# Project.net
KiCad netlist of a schematic drawn in EAGLE
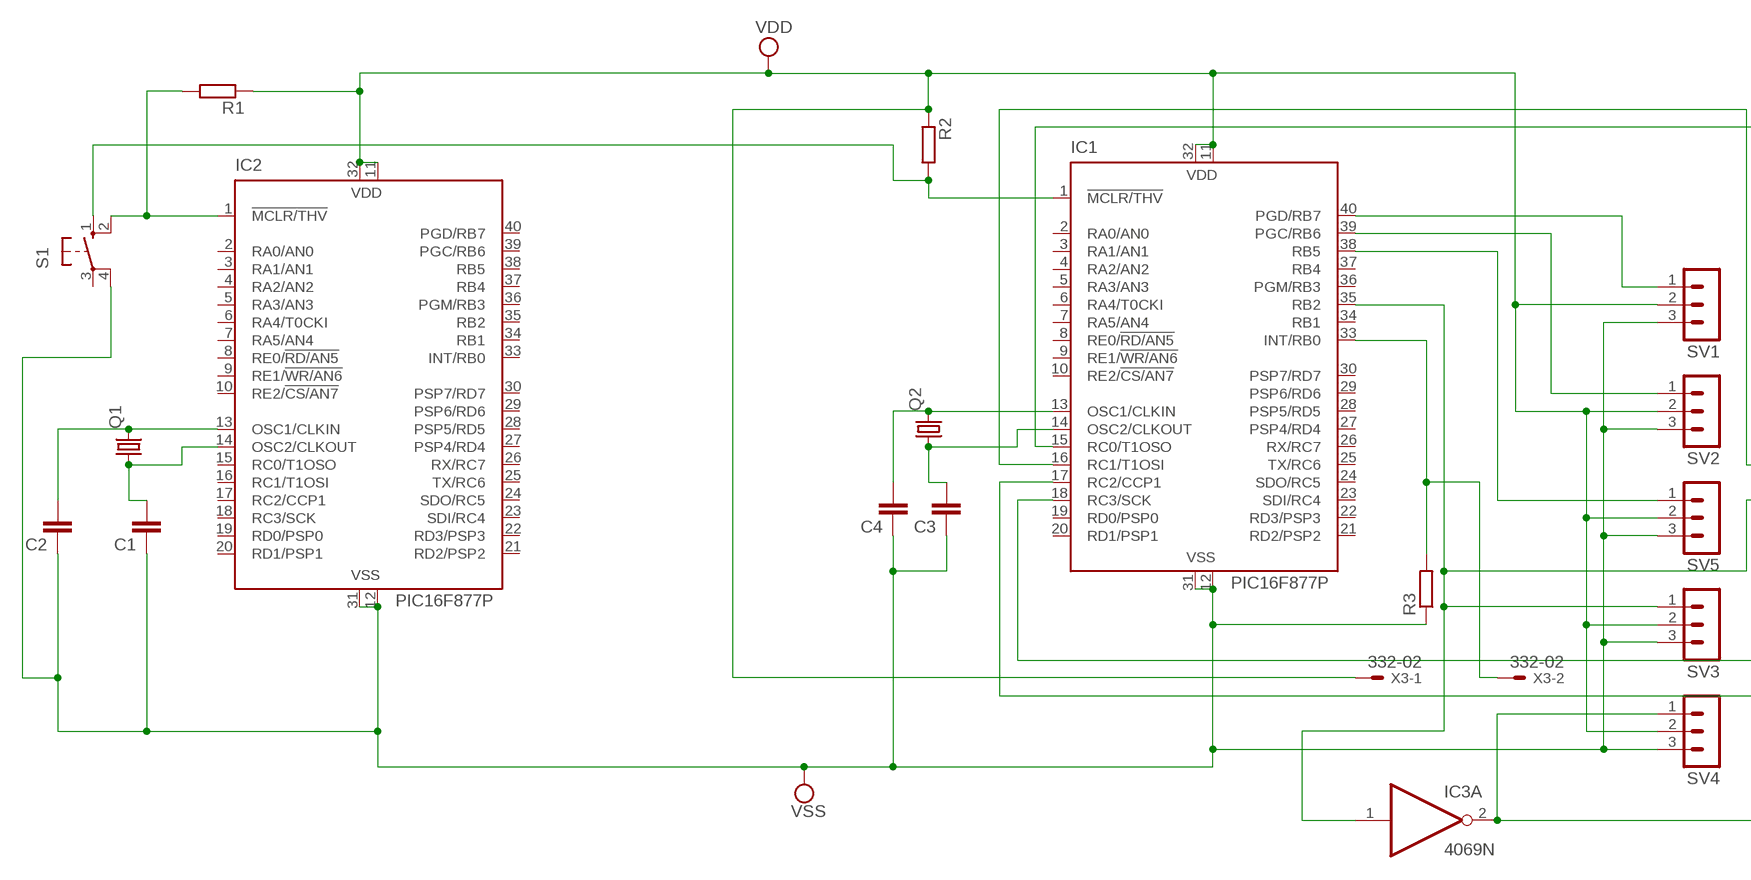
[diagram p0: schematic, sheet 1, part 1 of 2]
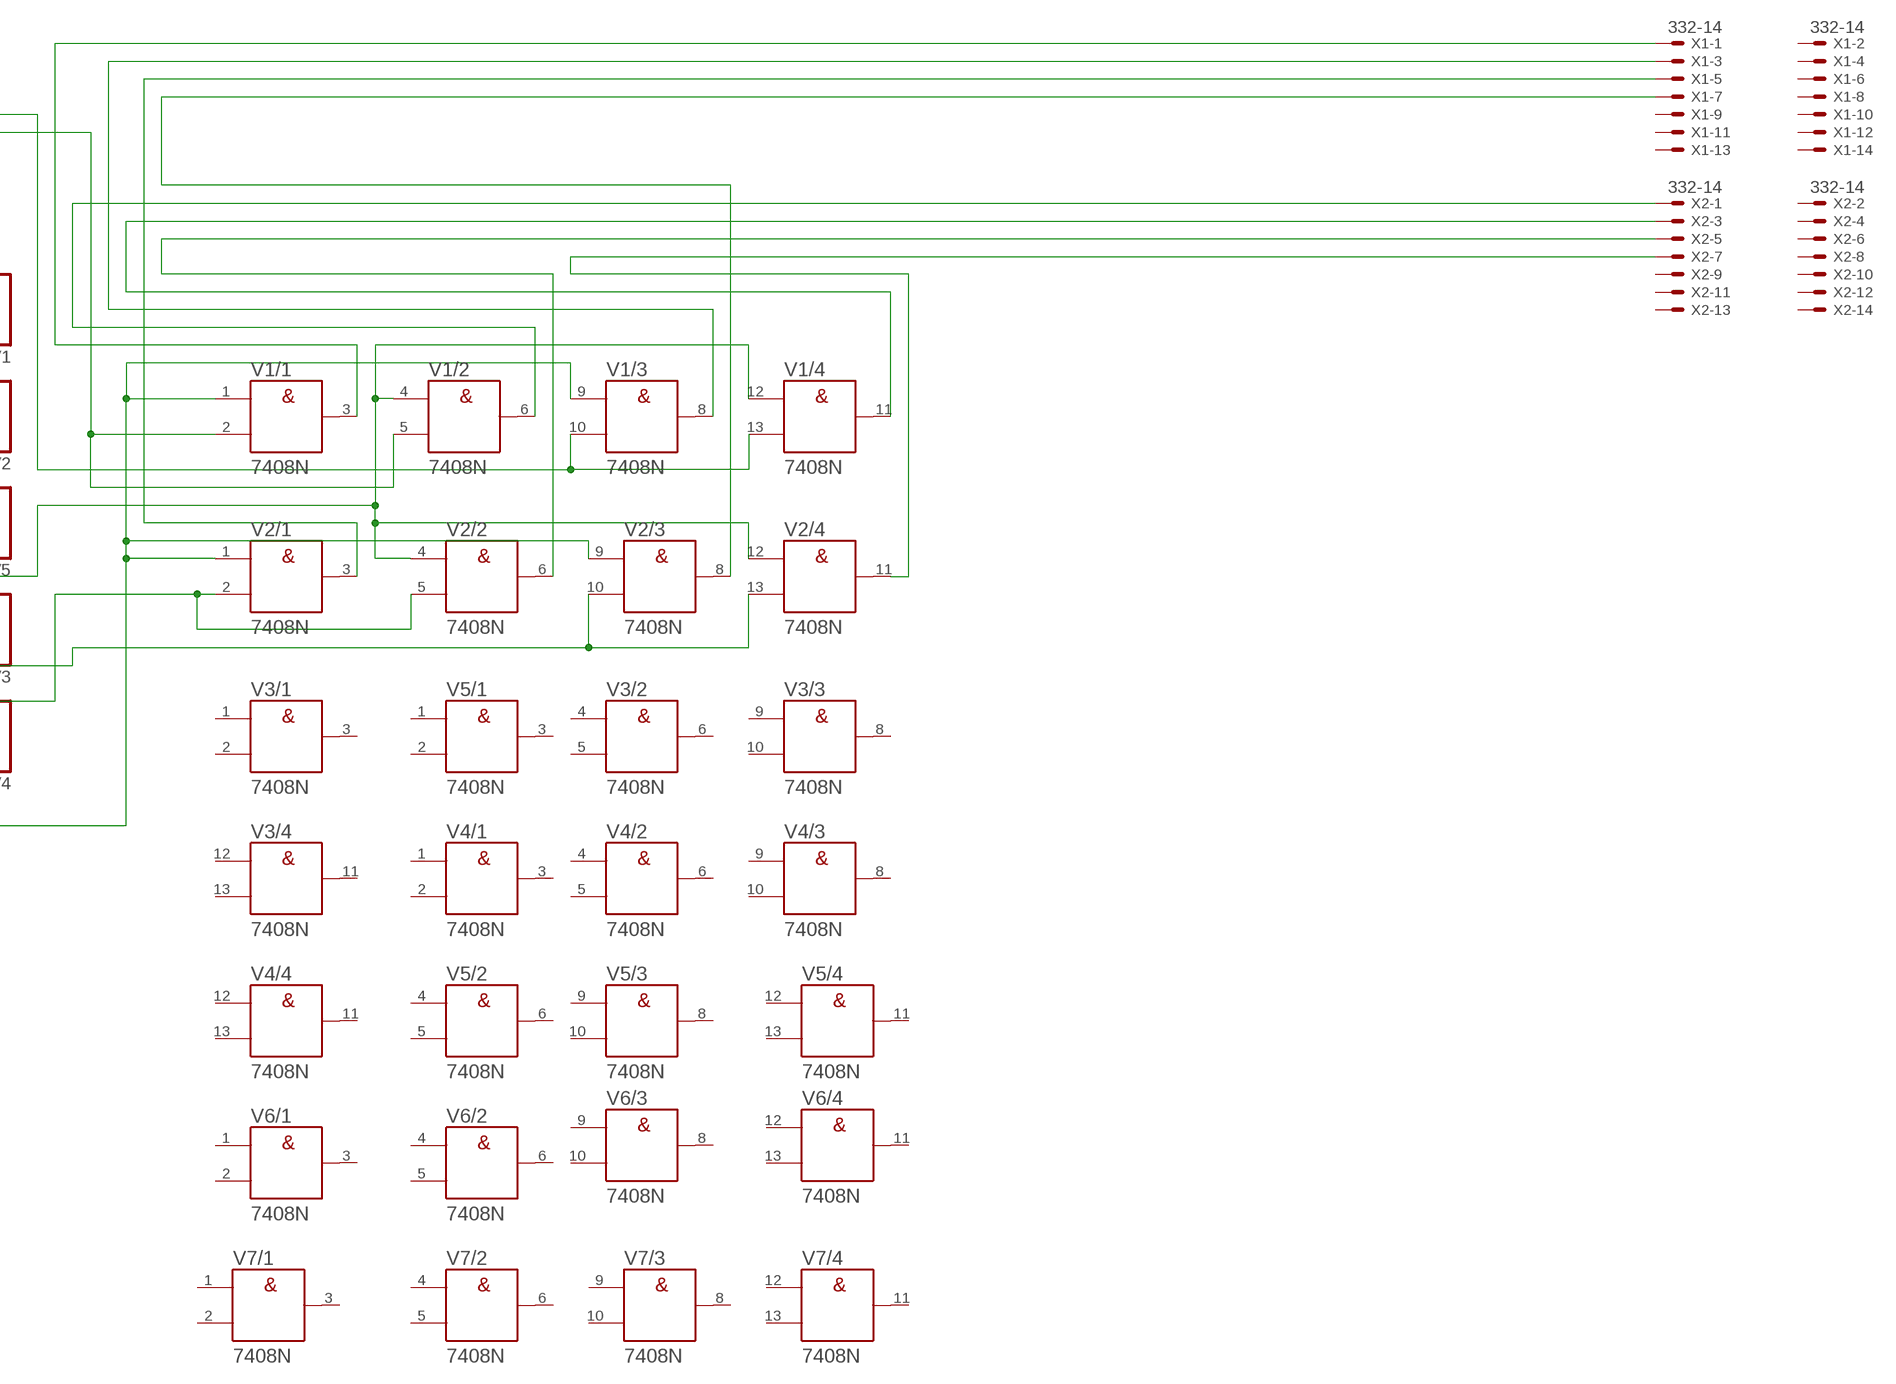
[diagram p1: schematic, sheet 1, part 2 of 2]

(export (version "E")
  (design (tool "Eeschema 10.0.6"))
  (components
    (comp (ref "C1")
      (value "C7.5/3")
      (footprint "eagle-import:C7.5B3")
      (libsource (lib "eagle-import") (part "C7.5/3"))
    )
    (comp (ref "C2")
      (value "C7.5/3")
      (footprint "eagle-import:C7.5B3")
      (libsource (lib "eagle-import") (part "C7.5/3"))
    )
    (comp (ref "C3")
      (value "C7.5/3")
      (footprint "eagle-import:C7.5B3")
      (libsource (lib "eagle-import") (part "C7.5/3"))
    )
    (comp (ref "C4")
      (value "C7.5/3")
      (footprint "eagle-import:C7.5B3")
      (libsource (lib "eagle-import") (part "C7.5/3"))
    )
    (comp (ref "IC1")
      (value "PIC16F877P")
      (footprint "eagle-import:DIL40")
      (fields (field (name "MF") "MICROCHIP") (field (name "MPN") "PIC16F877-04/P"))
      (libsource (lib "eagle-import") (part "PIC16F87P7"))
    )
    (comp (ref "IC2")
      (value "PIC16F877P")
      (footprint "eagle-import:DIL40")
      (fields (field (name "MF") "MICROCHIP") (field (name "MPN") "PIC16F877-04/P"))
      (libsource (lib "eagle-import") (part "PIC16F87P7"))
    )
    (comp (ref "IC3")
      (value "4069N")
      (footprint "eagle-import:DIL14")
      (libsource (lib "eagle-import") (part "4069N"))
    )
    (comp (ref "Q1")
      (value "CRYSTALHC49U-V")
      (footprint "eagle-import:HC49U-V")
      (libsource (lib "eagle-import") (part "CRYSTALHC49U-V"))
    )
    (comp (ref "Q2")
      (value "CRYSTALHC49U-V")
      (footprint "eagle-import:HC49U-V")
      (libsource (lib "eagle-import") (part "CRYSTALHC49U-V"))
    )
    (comp (ref "R1")
      (value "R-EU_0207/10")
      (footprint "eagle-import:0207_10")
      (libsource (lib "eagle-import") (part "R-EU_0207/10"))
    )
    (comp (ref "R2")
      (value "R-EU_0207/10")
      (footprint "eagle-import:0207_10")
      (libsource (lib "eagle-import") (part "R-EU_0207/10"))
    )
    (comp (ref "R3")
      (value "R-EU_0207/10")
      (footprint "eagle-import:0207_10")
      (libsource (lib "eagle-import") (part "R-EU_0207/10"))
    )
    (comp (ref "S1")
      (value "10-XX")
      (footprint "eagle-import:B3F-10XX")
      (fields (field (name "MPN") "B3F-1000"))
      (libsource (lib "eagle-import") (part "10-XX"))
    )
    (comp (ref "SV1")
      (value "MA03-1")
      (footprint "eagle-import:MA03-1")
      (libsource (lib "eagle-import") (part "MA03-1"))
    )
    (comp (ref "SV2")
      (value "MA03-1")
      (footprint "eagle-import:MA03-1")
      (libsource (lib "eagle-import") (part "MA03-1"))
    )
    (comp (ref "SV3")
      (value "MA03-1")
      (footprint "eagle-import:MA03-1")
      (libsource (lib "eagle-import") (part "MA03-1"))
    )
    (comp (ref "SV4")
      (value "MA03-1")
      (footprint "eagle-import:MA03-1")
      (libsource (lib "eagle-import") (part "MA03-1"))
    )
    (comp (ref "SV5")
      (value "MA03-1")
      (footprint "eagle-import:MA03-1")
      (libsource (lib "eagle-import") (part "MA03-1"))
    )
    (comp (ref "V1")
      (value "7408N")
      (footprint "eagle-import:DIL14")
      (libsource (lib "eagle-import") (part "7408N"))
    )
    (comp (ref "V2")
      (value "7408N")
      (footprint "eagle-import:DIL14")
      (libsource (lib "eagle-import") (part "7408N"))
    )
    (comp (ref "V3")
      (value "7408N")
      (footprint "eagle-import:DIL14")
      (libsource (lib "eagle-import") (part "7408N"))
    )
    (comp (ref "V4")
      (value "7408N")
      (footprint "eagle-import:DIL14")
      (libsource (lib "eagle-import") (part "7408N"))
    )
    (comp (ref "V5")
      (value "7408N")
      (footprint "eagle-import:DIL14")
      (libsource (lib "eagle-import") (part "7408N"))
    )
    (comp (ref "V6")
      (value "7408N")
      (footprint "eagle-import:DIL14")
      (libsource (lib "eagle-import") (part "7408N"))
    )
    (comp (ref "V7")
      (value "7408N")
      (footprint "eagle-import:DIL14")
      (libsource (lib "eagle-import") (part "7408N"))
    )
    (comp (ref "X1")
      (value "332-14")
      (footprint "eagle-import:332-14")
      (libsource (lib "eagle-import") (part "332-14"))
    )
    (comp (ref "X2")
      (value "332-14")
      (footprint "eagle-import:332-14")
      (libsource (lib "eagle-import") (part "332-14"))
    )
    (comp (ref "X3")
      (value "332-02")
      (footprint "eagle-import:332-02")
      (libsource (lib "eagle-import") (part "332-02"))
    )
  )
  (nets
    (net (code "1") (name "Net-(IC1-INT{slash}RB0)") (class "Default")
      (node (ref "IC1") (pin "33") (pinfunction "INT/RB0_33") (pintype "bidirectional"))
      (node (ref "R3") (pin "2") (pinfunction "2_2") (pintype "passive"))
      (node (ref "X3") (pin "2") (pinfunction "S_2") (pintype "passive"))
    )
    (net (code "2") (name "Net-(IC1-OSC1{slash}CLKIN)") (class "Default")
      (node (ref "C4") (pin "2") (pinfunction "2_2") (pintype "passive"))
      (node (ref "IC1") (pin "13") (pinfunction "OSC1/CLKIN_13") (pintype "input"))
      (node (ref "Q2") (pin "2") (pinfunction "2_2") (pintype "passive"))
    )
    (net (code "3") (name "Net-(IC1-OSC2{slash}CLKOUT)") (class "Default")
      (node (ref "C3") (pin "2") (pinfunction "2_2") (pintype "passive"))
      (node (ref "IC1") (pin "14") (pinfunction "OSC2/CLKOUT_14") (pintype "output"))
      (node (ref "Q2") (pin "1") (pinfunction "1_1") (pintype "passive"))
    )
    (net (code "4") (name "Net-(IC1-PGC{slash}RB6)") (class "Default")
      (node (ref "IC1") (pin "39") (pinfunction "PGC/RB6_39") (pintype "bidirectional"))
      (node (ref "SV2") (pin "1") (pinfunction "1_1") (pintype "passive"))
    )
    (net (code "5") (name "Net-(IC1-PGD{slash}RB7)") (class "Default")
      (node (ref "IC1") (pin "40") (pinfunction "PGD/RB7_40") (pintype "bidirectional"))
      (node (ref "SV1") (pin "1") (pinfunction "1_1") (pintype "passive"))
    )
    (net (code "6") (name "Net-(IC1-RB2)") (class "Default")
      (node (ref "IC1") (pin "35") (pinfunction "RB2_35") (pintype "bidirectional"))
      (node (ref "IC3") (pin "1") (pinfunction "I_1") (pintype "input"))
      (node (ref "SV3") (pin "1") (pinfunction "1_1") (pintype "passive"))
      (node (ref "V1") (pin "12") (pinfunction "A_12") (pintype "input"))
      (node (ref "V1") (pin "4") (pinfunction "A_4") (pintype "input"))
      (node (ref "V2") (pin "12") (pinfunction "A_12") (pintype "input"))
      (node (ref "V2") (pin "4") (pinfunction "A_4") (pintype "input"))
    )
    (net (code "7") (name "Net-(IC1-RB5)") (class "Default")
      (node (ref "IC1") (pin "38") (pinfunction "RB5_38") (pintype "bidirectional"))
      (node (ref "SV5") (pin "1") (pinfunction "1_1") (pintype "passive"))
    )
    (net (code "8") (name "Net-(IC1-RC0{slash}T1OSO)") (class "Default")
      (node (ref "IC1") (pin "15") (pinfunction "RC0/T1OSO_15") (pintype "bidirectional"))
      (node (ref "V1") (pin "2") (pinfunction "B_2") (pintype "input"))
      (node (ref "V1") (pin "5") (pinfunction "B_5") (pintype "input"))
    )
    (net (code "9") (name "Net-(IC1-RC1{slash}T1OSI)") (class "Default")
      (node (ref "IC1") (pin "16") (pinfunction "RC1/T1OSI_16") (pintype "bidirectional"))
      (node (ref "V1") (pin "10") (pinfunction "B_10") (pintype "input"))
      (node (ref "V1") (pin "13") (pinfunction "B_13") (pintype "input"))
    )
    (net (code "10") (name "Net-(IC1-RC2{slash}CCP1)") (class "Default")
      (node (ref "IC1") (pin "17") (pinfunction "RC2/CCP1_17") (pintype "bidirectional"))
      (node (ref "V2") (pin "2") (pinfunction "B_2") (pintype "input"))
      (node (ref "V2") (pin "5") (pinfunction "B_5") (pintype "input"))
    )
    (net (code "11") (name "Net-(IC1-RC3{slash}SCK)") (class "Default")
      (node (ref "IC1") (pin "18") (pinfunction "RC3/SCK_18") (pintype "bidirectional"))
      (node (ref "V2") (pin "10") (pinfunction "B_10") (pintype "input"))
      (node (ref "V2") (pin "13") (pinfunction "B_13") (pintype "input"))
    )
    (net (code "12") (name "Net-(IC1-~{MCLR{slash}THV})") (class "Default")
      (node (ref "IC1") (pin "1") (pinfunction "~{MCLR/THV}_1") (pintype "input"))
      (node (ref "R2") (pin "2") (pinfunction "2_2") (pintype "passive"))
      (node (ref "S1") (pin "1") (pinfunction "S_1") (pintype "passive"))
    )
    (net (code "13") (name "Net-(IC2-OSC1{slash}CLKIN)") (class "Default")
      (node (ref "C2") (pin "2") (pinfunction "2_2") (pintype "passive"))
      (node (ref "IC2") (pin "13") (pinfunction "OSC1/CLKIN_13") (pintype "input"))
      (node (ref "Q1") (pin "2") (pinfunction "2_2") (pintype "passive"))
    )
    (net (code "14") (name "Net-(IC2-OSC2{slash}CLKOUT)") (class "Default")
      (node (ref "C1") (pin "2") (pinfunction "2_2") (pintype "passive"))
      (node (ref "IC2") (pin "14") (pinfunction "OSC2/CLKOUT_14") (pintype "output"))
      (node (ref "Q1") (pin "1") (pinfunction "1_1") (pintype "passive"))
    )
    (net (code "15") (name "Net-(IC2-~{MCLR{slash}THV})") (class "Default")
      (node (ref "IC2") (pin "1") (pinfunction "~{MCLR/THV}_1") (pintype "input"))
      (node (ref "R1") (pin "2") (pinfunction "2_2") (pintype "passive"))
      (node (ref "S1") (pin "2") (pinfunction "S1_2") (pintype "passive"))
    )
    (net (code "16") (name "Net-(IC3A-O)") (class "Default")
      (node (ref "IC3") (pin "2") (pinfunction "O_2") (pintype "output"))
      (node (ref "SV4") (pin "1") (pinfunction "1_1") (pintype "passive"))
      (node (ref "V1") (pin "1") (pinfunction "A_1") (pintype "input"))
      (node (ref "V1") (pin "9") (pinfunction "A_9") (pintype "input"))
      (node (ref "V2") (pin "1") (pinfunction "A_1") (pintype "input"))
      (node (ref "V2") (pin "9") (pinfunction "A_9") (pintype "input"))
    )
    (net (code "17") (name "Net-(V1C-Y)") (class "Default")
      (node (ref "V1") (pin "3") (pinfunction "Y_3") (pintype "output"))
      (node (ref "X1") (pin "1") (pinfunction "S_1") (pintype "passive"))
    )
    (net (code "18") (name "Net-(V1D-Y)") (class "Default")
      (node (ref "V1") (pin "6") (pinfunction "Y_6") (pintype "output"))
      (node (ref "X2") (pin "1") (pinfunction "S_1") (pintype "passive"))
    )
    (net (code "19") (name "Net-(V1E-Y)") (class "Default")
      (node (ref "V1") (pin "8") (pinfunction "Y_8") (pintype "output"))
      (node (ref "X1") (pin "3") (pinfunction "S_3") (pintype "passive"))
    )
    (net (code "20") (name "Net-(V1F-Y)") (class "Default")
      (node (ref "V1") (pin "11") (pinfunction "Y_11") (pintype "output"))
      (node (ref "X2") (pin "3") (pinfunction "S_3") (pintype "passive"))
    )
    (net (code "21") (name "Net-(V2C-Y)") (class "Default")
      (node (ref "V2") (pin "3") (pinfunction "Y_3") (pintype "output"))
      (node (ref "X1") (pin "5") (pinfunction "S_5") (pintype "passive"))
    )
    (net (code "22") (name "Net-(V2D-Y)") (class "Default")
      (node (ref "V2") (pin "6") (pinfunction "Y_6") (pintype "output"))
      (node (ref "X2") (pin "5") (pinfunction "S_5") (pintype "passive"))
    )
    (net (code "23") (name "Net-(V2E-Y)") (class "Default")
      (node (ref "V2") (pin "8") (pinfunction "Y_8") (pintype "output"))
      (node (ref "X1") (pin "7") (pinfunction "S_7") (pintype "passive"))
    )
    (net (code "24") (name "Net-(V2F-Y)") (class "Default")
      (node (ref "V2") (pin "11") (pinfunction "Y_11") (pintype "output"))
      (node (ref "X2") (pin "7") (pinfunction "S_7") (pintype "passive"))
    )
    (net (code "25") (name "VDD") (class "Default")
      (node (ref "IC1") (pin "11") (pinfunction "VDD_11") (pintype "power_in"))
      (node (ref "IC1") (pin "32") (pinfunction "VDD_32") (pintype "power_in"))
      (node (ref "IC2") (pin "11") (pinfunction "VDD_11") (pintype "power_in"))
      (node (ref "IC2") (pin "32") (pinfunction "VDD_32") (pintype "power_in"))
      (node (ref "R1") (pin "1") (pinfunction "1_1") (pintype "passive"))
      (node (ref "R2") (pin "1") (pinfunction "1_1") (pintype "passive"))
      (node (ref "SV1") (pin "2") (pinfunction "2_2") (pintype "passive"))
      (node (ref "SV2") (pin "2") (pinfunction "2_2") (pintype "passive"))
      (node (ref "SV3") (pin "2") (pinfunction "2_2") (pintype "passive"))
      (node (ref "SV4") (pin "2") (pinfunction "2_2") (pintype "passive"))
      (node (ref "SV5") (pin "2") (pinfunction "2_2") (pintype "passive"))
      (node (ref "X3") (pin "1") (pinfunction "S_1") (pintype "passive"))
    )
    (net (code "26") (name "VSS") (class "Default")
      (node (ref "C1") (pin "1") (pinfunction "1_1") (pintype "passive"))
      (node (ref "C2") (pin "1") (pinfunction "1_1") (pintype "passive"))
      (node (ref "C3") (pin "1") (pinfunction "1_1") (pintype "passive"))
      (node (ref "C4") (pin "1") (pinfunction "1_1") (pintype "passive"))
      (node (ref "IC1") (pin "12") (pinfunction "VSS_12") (pintype "power_in"))
      (node (ref "IC1") (pin "31") (pinfunction "VSS_31") (pintype "power_in"))
      (node (ref "IC2") (pin "12") (pinfunction "VSS_12") (pintype "power_in"))
      (node (ref "IC2") (pin "31") (pinfunction "VSS_31") (pintype "power_in"))
      (node (ref "R3") (pin "1") (pinfunction "1_1") (pintype "passive"))
      (node (ref "S1") (pin "4") (pinfunction "P1_4") (pintype "passive"))
      (node (ref "SV1") (pin "3") (pinfunction "3_3") (pintype "passive"))
      (node (ref "SV2") (pin "3") (pinfunction "3_3") (pintype "passive"))
      (node (ref "SV3") (pin "3") (pinfunction "3_3") (pintype "passive"))
      (node (ref "SV4") (pin "3") (pinfunction "3_3") (pintype "passive"))
      (node (ref "SV5") (pin "3") (pinfunction "3_3") (pintype "passive"))
    )
    (net (code "27") (name "unconnected-(IC1-PGM{slash}RB3-Pad36)") (class "Default")
      (node (ref "IC1") (pin "36") (pinfunction "PGM/RB3_36") (pintype "bidirectional"))
    )
    (net (code "28") (name "unconnected-(IC1-PSP4{slash}RD4-Pad27)") (class "Default")
      (node (ref "IC1") (pin "27") (pinfunction "PSP4/RD4_27") (pintype "bidirectional"))
    )
    (net (code "29") (name "unconnected-(IC1-PSP5{slash}RD5-Pad28)") (class "Default")
      (node (ref "IC1") (pin "28") (pinfunction "PSP5/RD5_28") (pintype "bidirectional"))
    )
    (net (code "30") (name "unconnected-(IC1-PSP6{slash}RD6-Pad29)") (class "Default")
      (node (ref "IC1") (pin "29") (pinfunction "PSP6/RD6_29") (pintype "bidirectional"))
    )
    (net (code "31") (name "unconnected-(IC1-PSP7{slash}RD7-Pad30)") (class "Default")
      (node (ref "IC1") (pin "30") (pinfunction "PSP7/RD7_30") (pintype "bidirectional"))
    )
    (net (code "32") (name "unconnected-(IC1-RA0{slash}AN0-Pad2)") (class "Default")
      (node (ref "IC1") (pin "2") (pinfunction "RA0/AN0_2") (pintype "bidirectional"))
    )
    (net (code "33") (name "unconnected-(IC1-RA1{slash}AN1-Pad3)") (class "Default")
      (node (ref "IC1") (pin "3") (pinfunction "RA1/AN1_3") (pintype "bidirectional"))
    )
    (net (code "34") (name "unconnected-(IC1-RA2{slash}AN2-Pad4)") (class "Default")
      (node (ref "IC1") (pin "4") (pinfunction "RA2/AN2_4") (pintype "bidirectional"))
    )
    (net (code "35") (name "unconnected-(IC1-RA3{slash}AN3-Pad5)") (class "Default")
      (node (ref "IC1") (pin "5") (pinfunction "RA3/AN3_5") (pintype "bidirectional"))
    )
    (net (code "36") (name "unconnected-(IC1-RA4{slash}T0CKI-Pad6)") (class "Default")
      (node (ref "IC1") (pin "6") (pinfunction "RA4/T0CKI_6") (pintype "bidirectional"))
    )
    (net (code "37") (name "unconnected-(IC1-RA5{slash}AN4-Pad7)") (class "Default")
      (node (ref "IC1") (pin "7") (pinfunction "RA5/AN4_7") (pintype "bidirectional"))
    )
    (net (code "38") (name "unconnected-(IC1-RB1-Pad34)") (class "Default")
      (node (ref "IC1") (pin "34") (pinfunction "RB1_34") (pintype "bidirectional"))
    )
    (net (code "39") (name "unconnected-(IC1-RB4-Pad37)") (class "Default")
      (node (ref "IC1") (pin "37") (pinfunction "RB4_37") (pintype "bidirectional"))
    )
    (net (code "40") (name "unconnected-(IC1-RD0{slash}PSP0-Pad19)") (class "Default")
      (node (ref "IC1") (pin "19") (pinfunction "RD0/PSP0_19") (pintype "bidirectional"))
    )
    (net (code "41") (name "unconnected-(IC1-RD1{slash}PSP1-Pad20)") (class "Default")
      (node (ref "IC1") (pin "20") (pinfunction "RD1/PSP1_20") (pintype "bidirectional"))
    )
    (net (code "42") (name "unconnected-(IC1-RD2{slash}PSP2-Pad21)") (class "Default")
      (node (ref "IC1") (pin "21") (pinfunction "RD2/PSP2_21") (pintype "bidirectional"))
    )
    (net (code "43") (name "unconnected-(IC1-RD3{slash}PSP3-Pad22)") (class "Default")
      (node (ref "IC1") (pin "22") (pinfunction "RD3/PSP3_22") (pintype "bidirectional"))
    )
    (net (code "44") (name "unconnected-(IC1-RE0{slash}~{RD{slash}AN5}-Pad8)") (class "Default")
      (node (ref "IC1") (pin "8") (pinfunction "RE0/~{RD/AN5}_8") (pintype "bidirectional"))
    )
    (net (code "45") (name "unconnected-(IC1-RE1{slash}~{WR{slash}AN6}-Pad9)") (class "Default")
      (node (ref "IC1") (pin "9") (pinfunction "RE1/~{WR/AN6}_9") (pintype "bidirectional"))
    )
    (net (code "46") (name "unconnected-(IC1-RE2{slash}~{CS{slash}AN7}-Pad10)") (class "Default")
      (node (ref "IC1") (pin "10") (pinfunction "RE2/~{CS/AN7}_10") (pintype "bidirectional"))
    )
    (net (code "47") (name "unconnected-(IC1-RX{slash}RC7-Pad26)") (class "Default")
      (node (ref "IC1") (pin "26") (pinfunction "RX/RC7_26") (pintype "bidirectional"))
    )
    (net (code "48") (name "unconnected-(IC1-SDI{slash}RC4-Pad23)") (class "Default")
      (node (ref "IC1") (pin "23") (pinfunction "SDI/RC4_23") (pintype "bidirectional"))
    )
    (net (code "49") (name "unconnected-(IC1-SDO{slash}RC5-Pad24)") (class "Default")
      (node (ref "IC1") (pin "24") (pinfunction "SDO/RC5_24") (pintype "bidirectional"))
    )
    (net (code "50") (name "unconnected-(IC1-TX{slash}RC6-Pad25)") (class "Default")
      (node (ref "IC1") (pin "25") (pinfunction "TX/RC6_25") (pintype "bidirectional"))
    )
    (net (code "51") (name "unconnected-(IC2-INT{slash}RB0-Pad33)") (class "Default")
      (node (ref "IC2") (pin "33") (pinfunction "INT/RB0_33") (pintype "bidirectional"))
    )
    (net (code "52") (name "unconnected-(IC2-PGC{slash}RB6-Pad39)") (class "Default")
      (node (ref "IC2") (pin "39") (pinfunction "PGC/RB6_39") (pintype "bidirectional"))
    )
    (net (code "53") (name "unconnected-(IC2-PGD{slash}RB7-Pad40)") (class "Default")
      (node (ref "IC2") (pin "40") (pinfunction "PGD/RB7_40") (pintype "bidirectional"))
    )
    (net (code "54") (name "unconnected-(IC2-PGM{slash}RB3-Pad36)") (class "Default")
      (node (ref "IC2") (pin "36") (pinfunction "PGM/RB3_36") (pintype "bidirectional"))
    )
    (net (code "55") (name "unconnected-(IC2-PSP4{slash}RD4-Pad27)") (class "Default")
      (node (ref "IC2") (pin "27") (pinfunction "PSP4/RD4_27") (pintype "bidirectional"))
    )
    (net (code "56") (name "unconnected-(IC2-PSP5{slash}RD5-Pad28)") (class "Default")
      (node (ref "IC2") (pin "28") (pinfunction "PSP5/RD5_28") (pintype "bidirectional"))
    )
    (net (code "57") (name "unconnected-(IC2-PSP6{slash}RD6-Pad29)") (class "Default")
      (node (ref "IC2") (pin "29") (pinfunction "PSP6/RD6_29") (pintype "bidirectional"))
    )
    (net (code "58") (name "unconnected-(IC2-PSP7{slash}RD7-Pad30)") (class "Default")
      (node (ref "IC2") (pin "30") (pinfunction "PSP7/RD7_30") (pintype "bidirectional"))
    )
    (net (code "59") (name "unconnected-(IC2-RA0{slash}AN0-Pad2)") (class "Default")
      (node (ref "IC2") (pin "2") (pinfunction "RA0/AN0_2") (pintype "bidirectional"))
    )
    (net (code "60") (name "unconnected-(IC2-RA1{slash}AN1-Pad3)") (class "Default")
      (node (ref "IC2") (pin "3") (pinfunction "RA1/AN1_3") (pintype "bidirectional"))
    )
    (net (code "61") (name "unconnected-(IC2-RA2{slash}AN2-Pad4)") (class "Default")
      (node (ref "IC2") (pin "4") (pinfunction "RA2/AN2_4") (pintype "bidirectional"))
    )
    (net (code "62") (name "unconnected-(IC2-RA3{slash}AN3-Pad5)") (class "Default")
      (node (ref "IC2") (pin "5") (pinfunction "RA3/AN3_5") (pintype "bidirectional"))
    )
    (net (code "63") (name "unconnected-(IC2-RA4{slash}T0CKI-Pad6)") (class "Default")
      (node (ref "IC2") (pin "6") (pinfunction "RA4/T0CKI_6") (pintype "bidirectional"))
    )
    (net (code "64") (name "unconnected-(IC2-RA5{slash}AN4-Pad7)") (class "Default")
      (node (ref "IC2") (pin "7") (pinfunction "RA5/AN4_7") (pintype "bidirectional"))
    )
    (net (code "65") (name "unconnected-(IC2-RB1-Pad34)") (class "Default")
      (node (ref "IC2") (pin "34") (pinfunction "RB1_34") (pintype "bidirectional"))
    )
    (net (code "66") (name "unconnected-(IC2-RB2-Pad35)") (class "Default")
      (node (ref "IC2") (pin "35") (pinfunction "RB2_35") (pintype "bidirectional"))
    )
    (net (code "67") (name "unconnected-(IC2-RB4-Pad37)") (class "Default")
      (node (ref "IC2") (pin "37") (pinfunction "RB4_37") (pintype "bidirectional"))
    )
    (net (code "68") (name "unconnected-(IC2-RB5-Pad38)") (class "Default")
      (node (ref "IC2") (pin "38") (pinfunction "RB5_38") (pintype "bidirectional"))
    )
    (net (code "69") (name "unconnected-(IC2-RC0{slash}T1OSO-Pad15)") (class "Default")
      (node (ref "IC2") (pin "15") (pinfunction "RC0/T1OSO_15") (pintype "bidirectional"))
    )
    (net (code "70") (name "unconnected-(IC2-RC1{slash}T1OSI-Pad16)") (class "Default")
      (node (ref "IC2") (pin "16") (pinfunction "RC1/T1OSI_16") (pintype "bidirectional"))
    )
    (net (code "71") (name "unconnected-(IC2-RC2{slash}CCP1-Pad17)") (class "Default")
      (node (ref "IC2") (pin "17") (pinfunction "RC2/CCP1_17") (pintype "bidirectional"))
    )
    (net (code "72") (name "unconnected-(IC2-RC3{slash}SCK-Pad18)") (class "Default")
      (node (ref "IC2") (pin "18") (pinfunction "RC3/SCK_18") (pintype "bidirectional"))
    )
    (net (code "73") (name "unconnected-(IC2-RD0{slash}PSP0-Pad19)") (class "Default")
      (node (ref "IC2") (pin "19") (pinfunction "RD0/PSP0_19") (pintype "bidirectional"))
    )
    (net (code "74") (name "unconnected-(IC2-RD1{slash}PSP1-Pad20)") (class "Default")
      (node (ref "IC2") (pin "20") (pinfunction "RD1/PSP1_20") (pintype "bidirectional"))
    )
    (net (code "75") (name "unconnected-(IC2-RD2{slash}PSP2-Pad21)") (class "Default")
      (node (ref "IC2") (pin "21") (pinfunction "RD2/PSP2_21") (pintype "bidirectional"))
    )
    (net (code "76") (name "unconnected-(IC2-RD3{slash}PSP3-Pad22)") (class "Default")
      (node (ref "IC2") (pin "22") (pinfunction "RD3/PSP3_22") (pintype "bidirectional"))
    )
    (net (code "77") (name "unconnected-(IC2-RE0{slash}~{RD{slash}AN5}-Pad8)") (class "Default")
      (node (ref "IC2") (pin "8") (pinfunction "RE0/~{RD/AN5}_8") (pintype "bidirectional"))
    )
    (net (code "78") (name "unconnected-(IC2-RE1{slash}~{WR{slash}AN6}-Pad9)") (class "Default")
      (node (ref "IC2") (pin "9") (pinfunction "RE1/~{WR/AN6}_9") (pintype "bidirectional"))
    )
    (net (code "79") (name "unconnected-(IC2-RE2{slash}~{CS{slash}AN7}-Pad10)") (class "Default")
      (node (ref "IC2") (pin "10") (pinfunction "RE2/~{CS/AN7}_10") (pintype "bidirectional"))
    )
    (net (code "80") (name "unconnected-(IC2-RX{slash}RC7-Pad26)") (class "Default")
      (node (ref "IC2") (pin "26") (pinfunction "RX/RC7_26") (pintype "bidirectional"))
    )
    (net (code "81") (name "unconnected-(IC2-SDI{slash}RC4-Pad23)") (class "Default")
      (node (ref "IC2") (pin "23") (pinfunction "SDI/RC4_23") (pintype "bidirectional"))
    )
    (net (code "82") (name "unconnected-(IC2-SDO{slash}RC5-Pad24)") (class "Default")
      (node (ref "IC2") (pin "24") (pinfunction "SDO/RC5_24") (pintype "bidirectional"))
    )
    (net (code "83") (name "unconnected-(IC2-TX{slash}RC6-Pad25)") (class "Default")
      (node (ref "IC2") (pin "25") (pinfunction "TX/RC6_25") (pintype "bidirectional"))
    )
    (net (code "84") (name "unconnected-(S1-P-Pad3)") (class "Default")
      (node (ref "S1") (pin "3") (pinfunction "P_3") (pintype "passive"))
    )
    (net (code "85") (name "unconnected-(V3C-A-Pad1)") (class "Default")
      (node (ref "V3") (pin "1") (pinfunction "A_1") (pintype "input"))
    )
    (net (code "86") (name "unconnected-(V3C-B-Pad2)") (class "Default")
      (node (ref "V3") (pin "2") (pinfunction "B_2") (pintype "input"))
    )
    (net (code "87") (name "unconnected-(V3C-Y-Pad3)") (class "Default")
      (node (ref "V3") (pin "3") (pinfunction "Y_3") (pintype "output"))
    )
    (net (code "88") (name "unconnected-(V3D-A-Pad4)") (class "Default")
      (node (ref "V3") (pin "4") (pinfunction "A_4") (pintype "input"))
    )
    (net (code "89") (name "unconnected-(V3D-B-Pad5)") (class "Default")
      (node (ref "V3") (pin "5") (pinfunction "B_5") (pintype "input"))
    )
    (net (code "90") (name "unconnected-(V3D-Y-Pad6)") (class "Default")
      (node (ref "V3") (pin "6") (pinfunction "Y_6") (pintype "output"))
    )
    (net (code "91") (name "unconnected-(V3E-A-Pad9)") (class "Default")
      (node (ref "V3") (pin "9") (pinfunction "A_9") (pintype "input"))
    )
    (net (code "92") (name "unconnected-(V3E-B-Pad10)") (class "Default")
      (node (ref "V3") (pin "10") (pinfunction "B_10") (pintype "input"))
    )
    (net (code "93") (name "unconnected-(V3E-Y-Pad8)") (class "Default")
      (node (ref "V3") (pin "8") (pinfunction "Y_8") (pintype "output"))
    )
    (net (code "94") (name "unconnected-(V3F-A-Pad12)") (class "Default")
      (node (ref "V3") (pin "12") (pinfunction "A_12") (pintype "input"))
    )
    (net (code "95") (name "unconnected-(V3F-B-Pad13)") (class "Default")
      (node (ref "V3") (pin "13") (pinfunction "B_13") (pintype "input"))
    )
    (net (code "96") (name "unconnected-(V3F-Y-Pad11)") (class "Default")
      (node (ref "V3") (pin "11") (pinfunction "Y_11") (pintype "output"))
    )
    (net (code "97") (name "unconnected-(V4C-A-Pad1)") (class "Default")
      (node (ref "V4") (pin "1") (pinfunction "A_1") (pintype "input"))
    )
    (net (code "98") (name "unconnected-(V4C-B-Pad2)") (class "Default")
      (node (ref "V4") (pin "2") (pinfunction "B_2") (pintype "input"))
    )
    (net (code "99") (name "unconnected-(V4C-Y-Pad3)") (class "Default")
      (node (ref "V4") (pin "3") (pinfunction "Y_3") (pintype "output"))
    )
    (net (code "100") (name "unconnected-(V4D-A-Pad4)") (class "Default")
      (node (ref "V4") (pin "4") (pinfunction "A_4") (pintype "input"))
    )
    (net (code "101") (name "unconnected-(V4D-B-Pad5)") (class "Default")
      (node (ref "V4") (pin "5") (pinfunction "B_5") (pintype "input"))
    )
    (net (code "102") (name "unconnected-(V4D-Y-Pad6)") (class "Default")
      (node (ref "V4") (pin "6") (pinfunction "Y_6") (pintype "output"))
    )
    (net (code "103") (name "unconnected-(V4E-A-Pad9)") (class "Default")
      (node (ref "V4") (pin "9") (pinfunction "A_9") (pintype "input"))
    )
    (net (code "104") (name "unconnected-(V4E-B-Pad10)") (class "Default")
      (node (ref "V4") (pin "10") (pinfunction "B_10") (pintype "input"))
    )
    (net (code "105") (name "unconnected-(V4E-Y-Pad8)") (class "Default")
      (node (ref "V4") (pin "8") (pinfunction "Y_8") (pintype "output"))
    )
    (net (code "106") (name "unconnected-(V4F-A-Pad12)") (class "Default")
      (node (ref "V4") (pin "12") (pinfunction "A_12") (pintype "input"))
    )
    (net (code "107") (name "unconnected-(V4F-B-Pad13)") (class "Default")
      (node (ref "V4") (pin "13") (pinfunction "B_13") (pintype "input"))
    )
    (net (code "108") (name "unconnected-(V4F-Y-Pad11)") (class "Default")
      (node (ref "V4") (pin "11") (pinfunction "Y_11") (pintype "output"))
    )
    (net (code "109") (name "unconnected-(V5C-A-Pad1)") (class "Default")
      (node (ref "V5") (pin "1") (pinfunction "A_1") (pintype "input"))
    )
    (net (code "110") (name "unconnected-(V5C-B-Pad2)") (class "Default")
      (node (ref "V5") (pin "2") (pinfunction "B_2") (pintype "input"))
    )
    (net (code "111") (name "unconnected-(V5C-Y-Pad3)") (class "Default")
      (node (ref "V5") (pin "3") (pinfunction "Y_3") (pintype "output"))
    )
    (net (code "112") (name "unconnected-(V5D-A-Pad4)") (class "Default")
      (node (ref "V5") (pin "4") (pinfunction "A_4") (pintype "input"))
    )
    (net (code "113") (name "unconnected-(V5D-B-Pad5)") (class "Default")
      (node (ref "V5") (pin "5") (pinfunction "B_5") (pintype "input"))
    )
    (net (code "114") (name "unconnected-(V5D-Y-Pad6)") (class "Default")
      (node (ref "V5") (pin "6") (pinfunction "Y_6") (pintype "output"))
    )
    (net (code "115") (name "unconnected-(V5E-A-Pad9)") (class "Default")
      (node (ref "V5") (pin "9") (pinfunction "A_9") (pintype "input"))
    )
    (net (code "116") (name "unconnected-(V5E-B-Pad10)") (class "Default")
      (node (ref "V5") (pin "10") (pinfunction "B_10") (pintype "input"))
    )
    (net (code "117") (name "unconnected-(V5E-Y-Pad8)") (class "Default")
      (node (ref "V5") (pin "8") (pinfunction "Y_8") (pintype "output"))
    )
    (net (code "118") (name "unconnected-(V5F-A-Pad12)") (class "Default")
      (node (ref "V5") (pin "12") (pinfunction "A_12") (pintype "input"))
    )
    (net (code "119") (name "unconnected-(V5F-B-Pad13)") (class "Default")
      (node (ref "V5") (pin "13") (pinfunction "B_13") (pintype "input"))
    )
    (net (code "120") (name "unconnected-(V5F-Y-Pad11)") (class "Default")
      (node (ref "V5") (pin "11") (pinfunction "Y_11") (pintype "output"))
    )
    (net (code "121") (name "unconnected-(V6C-A-Pad1)") (class "Default")
      (node (ref "V6") (pin "1") (pinfunction "A_1") (pintype "input"))
    )
    (net (code "122") (name "unconnected-(V6C-B-Pad2)") (class "Default")
      (node (ref "V6") (pin "2") (pinfunction "B_2") (pintype "input"))
    )
    (net (code "123") (name "unconnected-(V6C-Y-Pad3)") (class "Default")
      (node (ref "V6") (pin "3") (pinfunction "Y_3") (pintype "output"))
    )
    (net (code "124") (name "unconnected-(V6D-A-Pad4)") (class "Default")
      (node (ref "V6") (pin "4") (pinfunction "A_4") (pintype "input"))
    )
    (net (code "125") (name "unconnected-(V6D-B-Pad5)") (class "Default")
      (node (ref "V6") (pin "5") (pinfunction "B_5") (pintype "input"))
    )
    (net (code "126") (name "unconnected-(V6D-Y-Pad6)") (class "Default")
      (node (ref "V6") (pin "6") (pinfunction "Y_6") (pintype "output"))
    )
    (net (code "127") (name "unconnected-(V6E-A-Pad9)") (class "Default")
      (node (ref "V6") (pin "9") (pinfunction "A_9") (pintype "input"))
    )
    (net (code "128") (name "unconnected-(V6E-B-Pad10)") (class "Default")
      (node (ref "V6") (pin "10") (pinfunction "B_10") (pintype "input"))
    )
    (net (code "129") (name "unconnected-(V6E-Y-Pad8)") (class "Default")
      (node (ref "V6") (pin "8") (pinfunction "Y_8") (pintype "output"))
    )
    (net (code "130") (name "unconnected-(V6F-A-Pad12)") (class "Default")
      (node (ref "V6") (pin "12") (pinfunction "A_12") (pintype "input"))
    )
    (net (code "131") (name "unconnected-(V6F-B-Pad13)") (class "Default")
      (node (ref "V6") (pin "13") (pinfunction "B_13") (pintype "input"))
    )
    (net (code "132") (name "unconnected-(V6F-Y-Pad11)") (class "Default")
      (node (ref "V6") (pin "11") (pinfunction "Y_11") (pintype "output"))
    )
    (net (code "133") (name "unconnected-(V7C-A-Pad1)") (class "Default")
      (node (ref "V7") (pin "1") (pinfunction "A_1") (pintype "input"))
    )
    (net (code "134") (name "unconnected-(V7C-B-Pad2)") (class "Default")
      (node (ref "V7") (pin "2") (pinfunction "B_2") (pintype "input"))
    )
    (net (code "135") (name "unconnected-(V7C-Y-Pad3)") (class "Default")
      (node (ref "V7") (pin "3") (pinfunction "Y_3") (pintype "output"))
    )
    (net (code "136") (name "unconnected-(V7D-A-Pad4)") (class "Default")
      (node (ref "V7") (pin "4") (pinfunction "A_4") (pintype "input"))
    )
    (net (code "137") (name "unconnected-(V7D-B-Pad5)") (class "Default")
      (node (ref "V7") (pin "5") (pinfunction "B_5") (pintype "input"))
    )
    (net (code "138") (name "unconnected-(V7D-Y-Pad6)") (class "Default")
      (node (ref "V7") (pin "6") (pinfunction "Y_6") (pintype "output"))
    )
    (net (code "139") (name "unconnected-(V7E-A-Pad9)") (class "Default")
      (node (ref "V7") (pin "9") (pinfunction "A_9") (pintype "input"))
    )
    (net (code "140") (name "unconnected-(V7E-B-Pad10)") (class "Default")
      (node (ref "V7") (pin "10") (pinfunction "B_10") (pintype "input"))
    )
    (net (code "141") (name "unconnected-(V7E-Y-Pad8)") (class "Default")
      (node (ref "V7") (pin "8") (pinfunction "Y_8") (pintype "output"))
    )
    (net (code "142") (name "unconnected-(V7F-A-Pad12)") (class "Default")
      (node (ref "V7") (pin "12") (pinfunction "A_12") (pintype "input"))
    )
    (net (code "143") (name "unconnected-(V7F-B-Pad13)") (class "Default")
      (node (ref "V7") (pin "13") (pinfunction "B_13") (pintype "input"))
    )
    (net (code "144") (name "unconnected-(V7F-Y-Pad11)") (class "Default")
      (node (ref "V7") (pin "11") (pinfunction "Y_11") (pintype "output"))
    )
    (net (code "145") (name "unconnected-(X1B-S-Pad10)") (class "Default")
      (node (ref "X1") (pin "10") (pinfunction "S_10") (pintype "passive"))
    )
    (net (code "146") (name "unconnected-(X1C-S-Pad11)") (class "Default")
      (node (ref "X1") (pin "11") (pinfunction "S_11") (pintype "passive"))
    )
    (net (code "147") (name "unconnected-(X1D-S-Pad12)") (class "Default")
      (node (ref "X1") (pin "12") (pinfunction "S_12") (pintype "passive"))
    )
    (net (code "148") (name "unconnected-(X1E-S-Pad13)") (class "Default")
      (node (ref "X1") (pin "13") (pinfunction "S_13") (pintype "passive"))
    )
    (net (code "149") (name "unconnected-(X1F-S-Pad14)") (class "Default")
      (node (ref "X1") (pin "14") (pinfunction "S_14") (pintype "passive"))
    )
    (net (code "150") (name "unconnected-(X1G-S-Pad2)") (class "Default")
      (node (ref "X1") (pin "2") (pinfunction "S_2") (pintype "passive"))
    )
    (net (code "151") (name "unconnected-(X1I-S-Pad4)") (class "Default")
      (node (ref "X1") (pin "4") (pinfunction "S_4") (pintype "passive"))
    )
    (net (code "152") (name "unconnected-(X1K-S-Pad6)") (class "Default")
      (node (ref "X1") (pin "6") (pinfunction "S_6") (pintype "passive"))
    )
    (net (code "153") (name "unconnected-(X1M-S-Pad8)") (class "Default")
      (node (ref "X1") (pin "8") (pinfunction "S_8") (pintype "passive"))
    )
    (net (code "154") (name "unconnected-(X1N-S-Pad9)") (class "Default")
      (node (ref "X1") (pin "9") (pinfunction "S_9") (pintype "passive"))
    )
    (net (code "155") (name "unconnected-(X2B-S-Pad10)") (class "Default")
      (node (ref "X2") (pin "10") (pinfunction "S_10") (pintype "passive"))
    )
    (net (code "156") (name "unconnected-(X2C-S-Pad11)") (class "Default")
      (node (ref "X2") (pin "11") (pinfunction "S_11") (pintype "passive"))
    )
    (net (code "157") (name "unconnected-(X2D-S-Pad12)") (class "Default")
      (node (ref "X2") (pin "12") (pinfunction "S_12") (pintype "passive"))
    )
    (net (code "158") (name "unconnected-(X2E-S-Pad13)") (class "Default")
      (node (ref "X2") (pin "13") (pinfunction "S_13") (pintype "passive"))
    )
    (net (code "159") (name "unconnected-(X2F-S-Pad14)") (class "Default")
      (node (ref "X2") (pin "14") (pinfunction "S_14") (pintype "passive"))
    )
    (net (code "160") (name "unconnected-(X2G-S-Pad2)") (class "Default")
      (node (ref "X2") (pin "2") (pinfunction "S_2") (pintype "passive"))
    )
    (net (code "161") (name "unconnected-(X2I-S-Pad4)") (class "Default")
      (node (ref "X2") (pin "4") (pinfunction "S_4") (pintype "passive"))
    )
    (net (code "162") (name "unconnected-(X2K-S-Pad6)") (class "Default")
      (node (ref "X2") (pin "6") (pinfunction "S_6") (pintype "passive"))
    )
    (net (code "163") (name "unconnected-(X2M-S-Pad8)") (class "Default")
      (node (ref "X2") (pin "8") (pinfunction "S_8") (pintype "passive"))
    )
    (net (code "164") (name "unconnected-(X2N-S-Pad9)") (class "Default")
      (node (ref "X2") (pin "9") (pinfunction "S_9") (pintype "passive"))
    )
  )
)
